# LORE.net
KiCad netlist of a schematic drawn in EAGLE
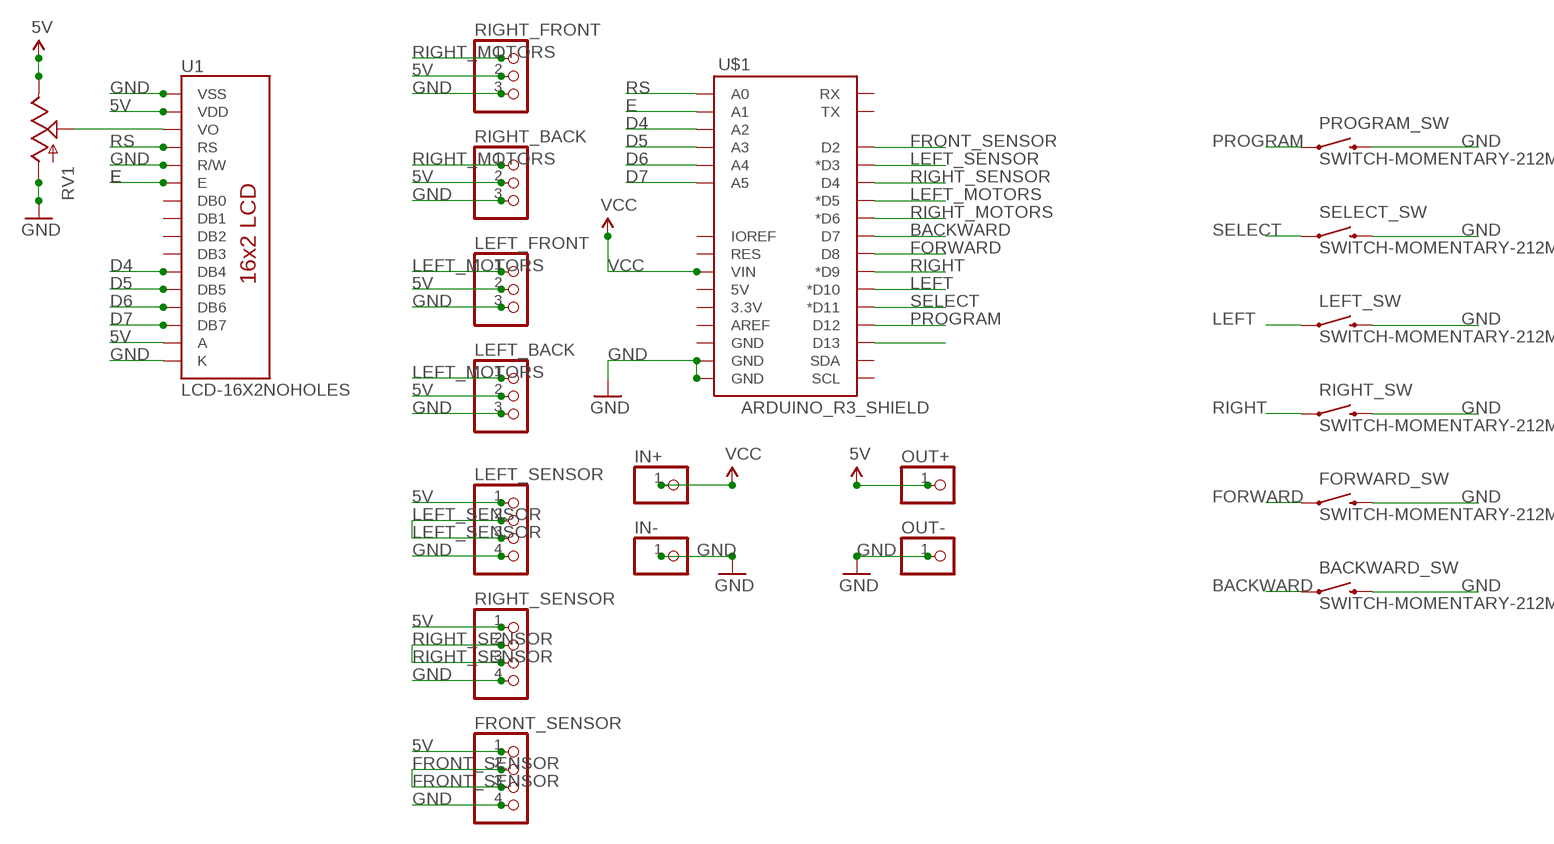
[diagram p0: schematic, sheet 1]

(export (version "E")
  (design (tool "Eeschema 10.0.6"))
  (components
    (comp (ref "BACKWARD_SW")
      (value "SWITCH-MOMENTARY-212MM")
      (footprint "eagle-import:TACTILE-PTH-12MM")
      (libsource (lib "eagle-import") (part "SWITCH-MOMENTARY-212MM"))
    )
    (comp (ref "FORWARD_SW")
      (value "SWITCH-MOMENTARY-212MM")
      (footprint "eagle-import:TACTILE-PTH-12MM")
      (libsource (lib "eagle-import") (part "SWITCH-MOMENTARY-212MM"))
    )
    (comp (ref "FRONT_SENSOR")
      (value "PINHD-1X4")
      (footprint "eagle-import:1X04")
      (libsource (lib "eagle-import") (part "PINHD-1X4"))
    )
    (comp (ref "IN+")
      (value "PINHD-1X1")
      (footprint "eagle-import:1X01")
      (libsource (lib "eagle-import") (part "PINHD-1X1"))
    )
    (comp (ref "IN-")
      (value "PINHD-1X1")
      (footprint "eagle-import:1X01")
      (libsource (lib "eagle-import") (part "PINHD-1X1"))
    )
    (comp (ref "LEFT_BACK")
      (value "PINHD-1X3")
      (footprint "eagle-import:1X03")
      (libsource (lib "eagle-import") (part "PINHD-1X3"))
    )
    (comp (ref "LEFT_FRONT")
      (value "PINHD-1X3")
      (footprint "eagle-import:1X03")
      (libsource (lib "eagle-import") (part "PINHD-1X3"))
    )
    (comp (ref "LEFT_SENSOR")
      (value "PINHD-1X4")
      (footprint "eagle-import:1X04")
      (libsource (lib "eagle-import") (part "PINHD-1X4"))
    )
    (comp (ref "LEFT_SW")
      (value "SWITCH-MOMENTARY-212MM")
      (footprint "eagle-import:TACTILE-PTH-12MM")
      (libsource (lib "eagle-import") (part "SWITCH-MOMENTARY-212MM"))
    )
    (comp (ref "OUT+")
      (value "PINHD-1X1")
      (footprint "eagle-import:1X01")
      (libsource (lib "eagle-import") (part "PINHD-1X1"))
    )
    (comp (ref "OUT-")
      (value "PINHD-1X1")
      (footprint "eagle-import:1X01")
      (libsource (lib "eagle-import") (part "PINHD-1X1"))
    )
    (comp (ref "PROGRAM_SW")
      (value "SWITCH-MOMENTARY-212MM")
      (footprint "eagle-import:TACTILE-PTH-12MM")
      (libsource (lib "eagle-import") (part "SWITCH-MOMENTARY-212MM"))
    )
    (comp (ref "RIGHT_BACK")
      (value "PINHD-1X3")
      (footprint "eagle-import:1X03")
      (libsource (lib "eagle-import") (part "PINHD-1X3"))
    )
    (comp (ref "RIGHT_FRONT")
      (value "PINHD-1X3")
      (footprint "eagle-import:1X03")
      (libsource (lib "eagle-import") (part "PINHD-1X3"))
    )
    (comp (ref "RIGHT_SENSOR")
      (value "PINHD-1X4")
      (footprint "eagle-import:1X04")
      (libsource (lib "eagle-import") (part "PINHD-1X4"))
    )
    (comp (ref "RIGHT_SW")
      (value "SWITCH-MOMENTARY-212MM")
      (footprint "eagle-import:TACTILE-PTH-12MM")
      (libsource (lib "eagle-import") (part "SWITCH-MOMENTARY-212MM"))
    )
    (comp (ref "RV1")
      (value "POTTRIM")
      (footprint "eagle-import:TRIM_POT")
      (libsource (lib "eagle-import") (part "POTTRIM"))
    )
    (comp (ref "SELECT_SW")
      (value "SWITCH-MOMENTARY-212MM")
      (footprint "eagle-import:TACTILE-PTH-12MM")
      (libsource (lib "eagle-import") (part "SWITCH-MOMENTARY-212MM"))
    )
    (comp (ref "U$1")
      (value "ARDUINO_R3_SHIELD")
      (footprint "eagle-import:UNO_R3_SHIELD")
      (libsource (lib "eagle-import") (part "ARDUINO_R3_SHIELD"))
    )
    (comp (ref "U1")
      (value "LCD-16X2NOHOLES")
      (footprint "eagle-import:LCD-16X2_NOHOLES")
      (libsource (lib "eagle-import") (part "LCD-16X2NOHOLES"))
    )
  )
  (nets
    (net (code "1") (name "/BACKWARD") (class "Default")
      (node (ref "BACKWARD_SW") (pin "1") (pinfunction "1_1") (pintype "passive"))
      (node (ref "U$1") (pin "D7") (pinfunction "D7_D7") (pintype "bidirectional"))
    )
    (net (code "2") (name "/D4") (class "Default")
      (node (ref "U$1") (pin "A2") (pinfunction "A2_A2") (pintype "bidirectional"))
      (node (ref "U1") (pin "11") (pinfunction "DB4_11") (pintype "bidirectional"))
    )
    (net (code "3") (name "/D5") (class "Default")
      (node (ref "U$1") (pin "A3") (pinfunction "A3_A3") (pintype "bidirectional"))
      (node (ref "U1") (pin "12") (pinfunction "DB5_12") (pintype "bidirectional"))
    )
    (net (code "4") (name "/D6") (class "Default")
      (node (ref "U$1") (pin "A4") (pinfunction "A4_A4") (pintype "bidirectional"))
      (node (ref "U1") (pin "13") (pinfunction "DB6_13") (pintype "bidirectional"))
    )
    (net (code "5") (name "/D7") (class "Default")
      (node (ref "U$1") (pin "A5") (pinfunction "A5_A5") (pintype "bidirectional"))
      (node (ref "U1") (pin "14") (pinfunction "DB7_14") (pintype "bidirectional"))
    )
    (net (code "6") (name "/E") (class "Default")
      (node (ref "U$1") (pin "A1") (pinfunction "A1_A1") (pintype "bidirectional"))
      (node (ref "U1") (pin "6") (pinfunction "E_6") (pintype "input"))
    )
    (net (code "7") (name "/FORWARD") (class "Default")
      (node (ref "FORWARD_SW") (pin "1") (pinfunction "1_1") (pintype "passive"))
      (node (ref "U$1") (pin "D8") (pinfunction "D8_D8") (pintype "bidirectional"))
    )
    (net (code "8") (name "/FRONT_SENSOR") (class "Default")
      (node (ref "FRONT_SENSOR") (pin "2") (pinfunction "2_2") (pintype "passive"))
      (node (ref "FRONT_SENSOR") (pin "3") (pinfunction "3_3") (pintype "passive"))
      (node (ref "U$1") (pin "D2") (pinfunction "D2_D2") (pintype "bidirectional"))
    )
    (net (code "9") (name "/LEFT") (class "Default")
      (node (ref "LEFT_SW") (pin "1") (pinfunction "1_1") (pintype "passive"))
      (node (ref "U$1") (pin "D10") (pinfunction "*D10_D10") (pintype "bidirectional"))
    )
    (net (code "10") (name "/LEFT_MOTORS") (class "Default")
      (node (ref "LEFT_BACK") (pin "1") (pinfunction "1_1") (pintype "passive"))
      (node (ref "LEFT_FRONT") (pin "1") (pinfunction "1_1") (pintype "passive"))
      (node (ref "U$1") (pin "D5") (pinfunction "*D5_D5") (pintype "bidirectional"))
    )
    (net (code "11") (name "/LEFT_SENSOR") (class "Default")
      (node (ref "LEFT_SENSOR") (pin "2") (pinfunction "2_2") (pintype "passive"))
      (node (ref "LEFT_SENSOR") (pin "3") (pinfunction "3_3") (pintype "passive"))
      (node (ref "U$1") (pin "D3") (pinfunction "*D3_D3") (pintype "bidirectional"))
    )
    (net (code "12") (name "/PROGRAM") (class "Default")
      (node (ref "PROGRAM_SW") (pin "1") (pinfunction "1_1") (pintype "passive"))
      (node (ref "U$1") (pin "D12") (pinfunction "D12_D12") (pintype "bidirectional"))
    )
    (net (code "13") (name "/RIGHT") (class "Default")
      (node (ref "RIGHT_SW") (pin "1") (pinfunction "1_1") (pintype "passive"))
      (node (ref "U$1") (pin "D9") (pinfunction "*D9_D9") (pintype "bidirectional"))
    )
    (net (code "14") (name "/RIGHT_MOTORS") (class "Default")
      (node (ref "RIGHT_BACK") (pin "1") (pinfunction "1_1") (pintype "passive"))
      (node (ref "RIGHT_FRONT") (pin "1") (pinfunction "1_1") (pintype "passive"))
      (node (ref "U$1") (pin "D6") (pinfunction "*D6_D6") (pintype "bidirectional"))
    )
    (net (code "15") (name "/RIGHT_SENSOR") (class "Default")
      (node (ref "RIGHT_SENSOR") (pin "2") (pinfunction "2_2") (pintype "passive"))
      (node (ref "RIGHT_SENSOR") (pin "3") (pinfunction "3_3") (pintype "passive"))
      (node (ref "U$1") (pin "D4") (pinfunction "D4_D4") (pintype "bidirectional"))
    )
    (net (code "16") (name "/RS") (class "Default")
      (node (ref "U$1") (pin "A0") (pinfunction "A0_A0") (pintype "bidirectional"))
      (node (ref "U1") (pin "4") (pinfunction "RS_4") (pintype "input"))
    )
    (net (code "17") (name "/SELECT") (class "Default")
      (node (ref "SELECT_SW") (pin "1") (pinfunction "1_1") (pintype "passive"))
      (node (ref "U$1") (pin "D11") (pinfunction "*D11_D11") (pintype "bidirectional"))
    )
    (net (code "18") (name "5V") (class "Default")
      (node (ref "FRONT_SENSOR") (pin "1") (pinfunction "1_1") (pintype "passive"))
      (node (ref "LEFT_BACK") (pin "2") (pinfunction "2_2") (pintype "passive"))
      (node (ref "LEFT_FRONT") (pin "2") (pinfunction "2_2") (pintype "passive"))
      (node (ref "LEFT_SENSOR") (pin "1") (pinfunction "1_1") (pintype "passive"))
      (node (ref "OUT+") (pin "1") (pinfunction "1_1") (pintype "passive"))
      (node (ref "RIGHT_BACK") (pin "2") (pinfunction "2_2") (pintype "passive"))
      (node (ref "RIGHT_FRONT") (pin "2") (pinfunction "2_2") (pintype "passive"))
      (node (ref "RIGHT_SENSOR") (pin "1") (pinfunction "1_1") (pintype "passive"))
      (node (ref "RV1") (pin "2") (pinfunction "E_2") (pintype "passive"))
      (node (ref "U1") (pin "15") (pinfunction "A_15") (pintype "power_in"))
      (node (ref "U1") (pin "2") (pinfunction "VDD_2") (pintype "power_in"))
    )
    (net (code "19") (name "GND") (class "Default")
      (node (ref "BACKWARD_SW") (pin "3") (pinfunction "2_3") (pintype "passive"))
      (node (ref "FORWARD_SW") (pin "3") (pinfunction "2_3") (pintype "passive"))
      (node (ref "FRONT_SENSOR") (pin "4") (pinfunction "4_4") (pintype "passive"))
      (node (ref "IN-") (pin "1") (pinfunction "1_1") (pintype "passive"))
      (node (ref "LEFT_BACK") (pin "3") (pinfunction "3_3") (pintype "passive"))
      (node (ref "LEFT_FRONT") (pin "3") (pinfunction "3_3") (pintype "passive"))
      (node (ref "LEFT_SENSOR") (pin "4") (pinfunction "4_4") (pintype "passive"))
      (node (ref "LEFT_SW") (pin "3") (pinfunction "2_3") (pintype "passive"))
      (node (ref "OUT-") (pin "1") (pinfunction "1_1") (pintype "passive"))
      (node (ref "PROGRAM_SW") (pin "3") (pinfunction "2_3") (pintype "passive"))
      (node (ref "RIGHT_BACK") (pin "3") (pinfunction "3_3") (pintype "passive"))
      (node (ref "RIGHT_FRONT") (pin "3") (pinfunction "3_3") (pintype "passive"))
      (node (ref "RIGHT_SENSOR") (pin "4") (pinfunction "4_4") (pintype "passive"))
      (node (ref "RIGHT_SW") (pin "3") (pinfunction "2_3") (pintype "passive"))
      (node (ref "RV1") (pin "3") (pinfunction "A_3") (pintype "passive"))
      (node (ref "SELECT_SW") (pin "3") (pinfunction "2_3") (pintype "passive"))
      (node (ref "U$1") (pin "GND@0") (pinfunction "GND_GND@0") (pintype "bidirectional"))
      (node (ref "U$1") (pin "GND@1") (pinfunction "GND_GND@1") (pintype "bidirectional"))
      (node (ref "U1") (pin "1") (pinfunction "VSS_1") (pintype "power_in"))
      (node (ref "U1") (pin "16") (pinfunction "K_16") (pintype "power_in"))
      (node (ref "U1") (pin "5") (pinfunction "R/W_5") (pintype "input"))
    )
    (net (code "20") (name "Net-(RV1-S)") (class "Default")
      (node (ref "RV1") (pin "1") (pinfunction "S_1") (pintype "passive"))
      (node (ref "U1") (pin "3") (pinfunction "VO_3") (pintype "bidirectional"))
    )
    (net (code "21") (name "VCC") (class "Default")
      (node (ref "IN+") (pin "1") (pinfunction "1_1") (pintype "passive"))
      (node (ref "U$1") (pin "VIN") (pinfunction "VIN_VIN") (pintype "bidirectional"))
    )
    (net (code "22") (name "unconnected-(U$1-GND-PadGND@2)") (class "Default")
      (node (ref "U$1") (pin "GND@2") (pinfunction "GND_GND@2") (pintype "bidirectional"))
    )
    (net (code "23") (name "unconnected-(U$1-Pad3.3V)") (class "Default")
      (node (ref "U$1") (pin "3.3V") (pinfunction "3.3V_3.3V") (pintype "bidirectional"))
    )
    (net (code "24") (name "unconnected-(U$1-Pad5V)") (class "Default")
      (node (ref "U$1") (pin "5V") (pinfunction "5V_5V") (pintype "bidirectional"))
    )
    (net (code "25") (name "unconnected-(U$1-PadAREF)") (class "Default")
      (node (ref "U$1") (pin "AREF") (pinfunction "AREF_AREF") (pintype "bidirectional"))
    )
    (net (code "26") (name "unconnected-(U$1-PadD13)") (class "Default")
      (node (ref "U$1") (pin "D13") (pinfunction "D13_D13") (pintype "bidirectional"))
    )
    (net (code "27") (name "unconnected-(U$1-PadIOREF)") (class "Default")
      (node (ref "U$1") (pin "IOREF") (pinfunction "IOREF_IOREF") (pintype "bidirectional"))
    )
    (net (code "28") (name "unconnected-(U$1-PadRES)") (class "Default")
      (node (ref "U$1") (pin "RES") (pinfunction "RES_RES") (pintype "bidirectional"))
    )
    (net (code "29") (name "unconnected-(U$1-PadRX)") (class "Default")
      (node (ref "U$1") (pin "RX") (pinfunction "RX_RX") (pintype "bidirectional"))
    )
    (net (code "30") (name "unconnected-(U$1-PadSCL)") (class "Default")
      (node (ref "U$1") (pin "SCL") (pinfunction "SCL_SCL") (pintype "bidirectional"))
    )
    (net (code "31") (name "unconnected-(U$1-PadSDA)") (class "Default")
      (node (ref "U$1") (pin "SDA") (pinfunction "SDA_SDA") (pintype "bidirectional"))
    )
    (net (code "32") (name "unconnected-(U$1-PadTX)") (class "Default")
      (node (ref "U$1") (pin "TX") (pinfunction "TX_TX") (pintype "bidirectional"))
    )
    (net (code "33") (name "unconnected-(U1-DB0-Pad7)") (class "Default")
      (node (ref "U1") (pin "7") (pinfunction "DB0_7") (pintype "bidirectional"))
    )
    (net (code "34") (name "unconnected-(U1-DB1-Pad8)") (class "Default")
      (node (ref "U1") (pin "8") (pinfunction "DB1_8") (pintype "bidirectional"))
    )
    (net (code "35") (name "unconnected-(U1-DB2-Pad9)") (class "Default")
      (node (ref "U1") (pin "9") (pinfunction "DB2_9") (pintype "bidirectional"))
    )
    (net (code "36") (name "unconnected-(U1-DB3-Pad10)") (class "Default")
      (node (ref "U1") (pin "10") (pinfunction "DB3_10") (pintype "bidirectional"))
    )
  )
)
